# 6Amp_DCDC.net
KiCad netlist of a schematic drawn in Altium Designer
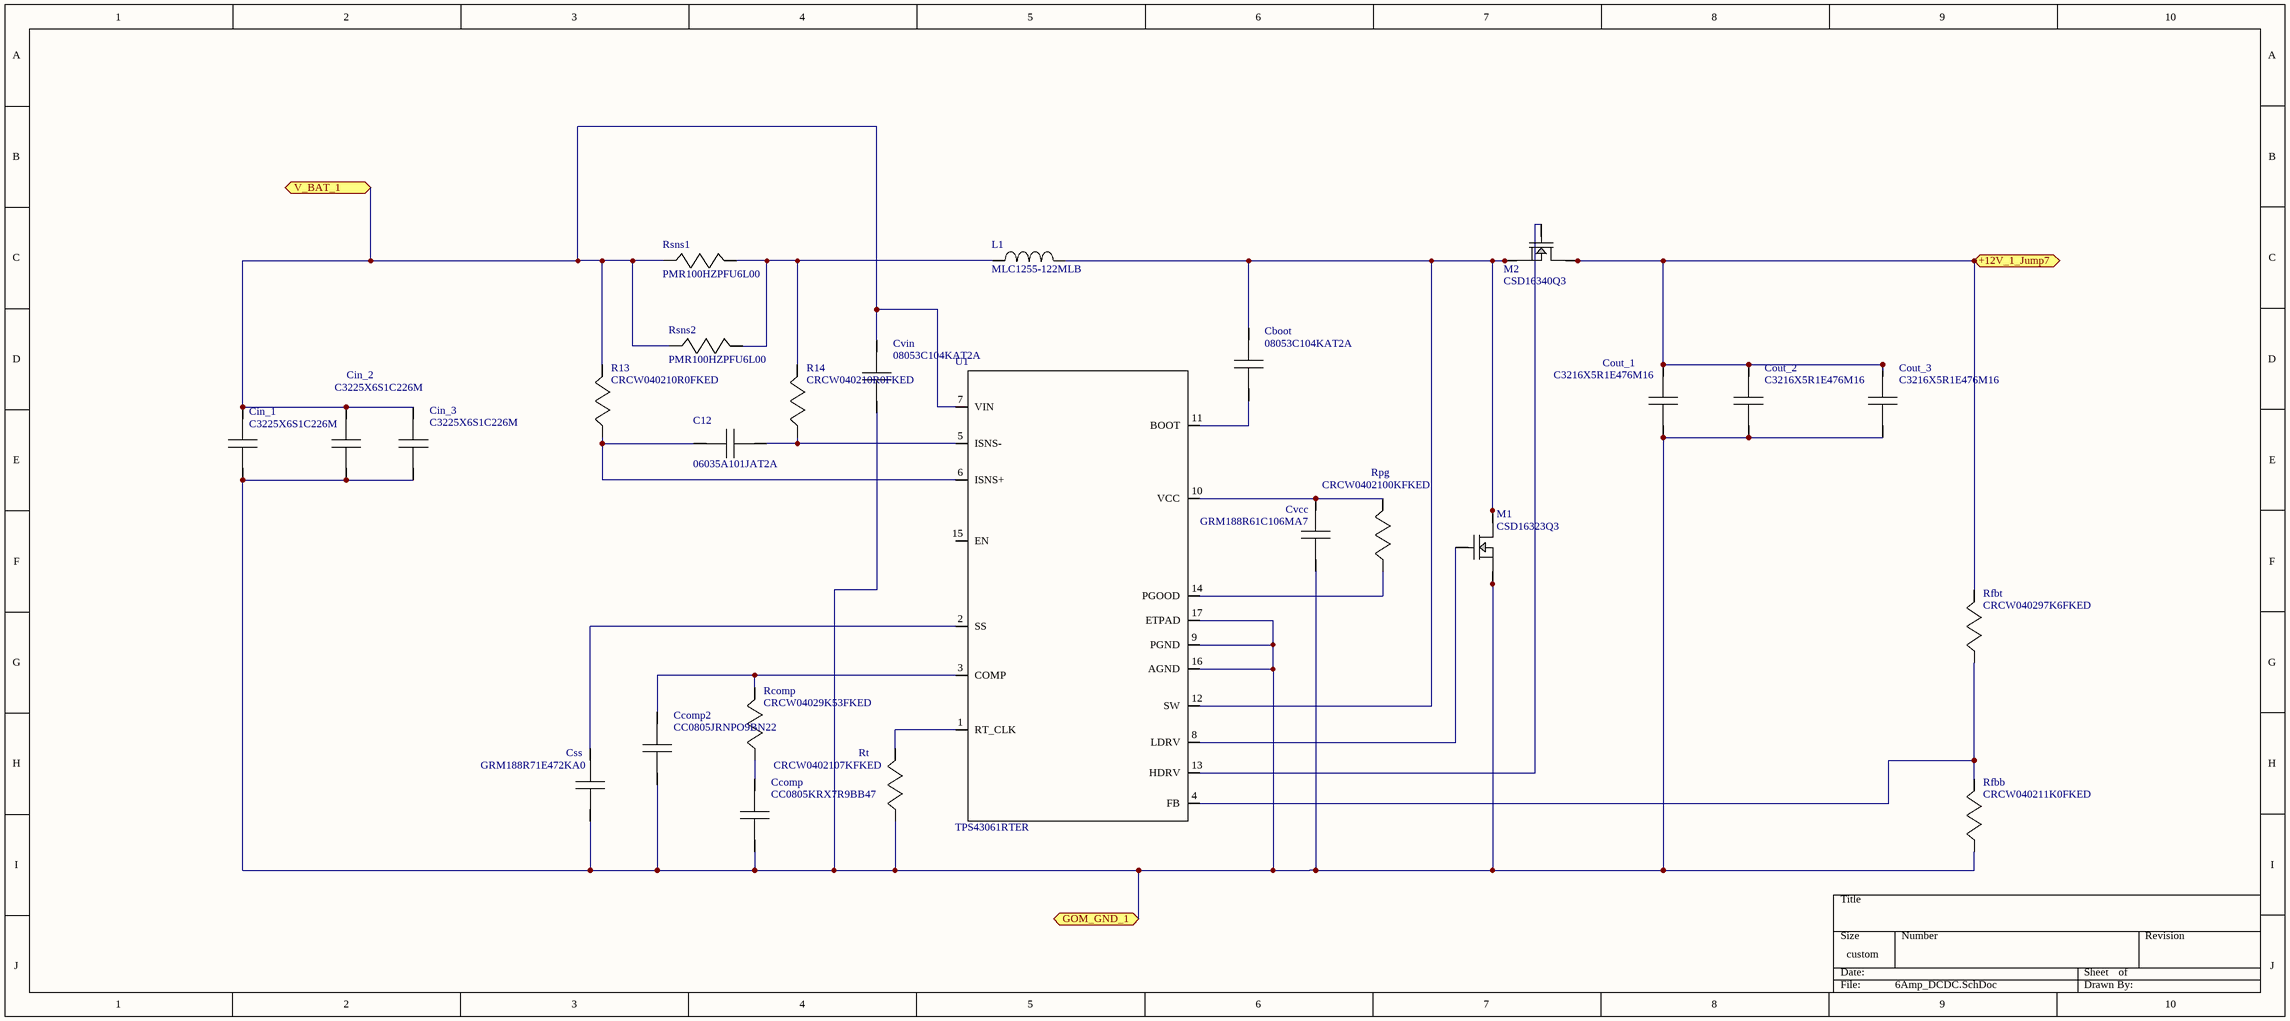
[diagram p0: 6Amp_DCDC.SchDoc]

(export (version "E")
  (design (tool "Eeschema 10.0.6"))
  (components
    (comp (ref "C12")
      (value "06035A101JAT2A")
      (footprint "0603")
      (description "Imported")
      (libsource (lib "2016-03-26_18-23-46") (part "06035A101JAT2A"))
    )
    (comp (ref "Cboot")
      (value "08053C104KAT2A")
      (footprint "0805")
      (description "Imported")
      (libsource (lib "2016-03-26_18-23-46") (part "08053C104KAT2A"))
    )
    (comp (ref "Ccomp")
      (value "CC0805KRX7R9BB47")
      (footprint "0805")
      (description "Imported")
      (fields (field (name "MANUFACTURER_PART_NUMBER") "CC0805KRX7R9BB472"))
      (libsource (lib "2016-03-26_18-23-46") (part "CC0805KRX7R9BB47"))
    )
    (comp (ref "Ccomp2")
      (value "CC0805JRNPO9BN22")
      (footprint "0805")
      (description "Imported")
      (fields (field (name "MANUFACTURER_PART_NUMBER") "CC0805JRNPO9BN221"))
      (libsource (lib "2016-03-26_18-23-46") (part "CC0805JRNPO9BN22"))
    )
    (comp (ref "Cin_1")
      (value "C3225X6S1C226M")
      (footprint "1210")
      (description "Imported")
      (libsource (lib "2016-03-26_18-23-46") (part "C3225X6S1C226M"))
    )
    (comp (ref "Cin_2")
      (value "C3225X6S1C226M")
      (footprint "1210")
      (description "Imported")
      (libsource (lib "2016-03-26_18-23-46") (part "C3225X6S1C226M"))
    )
    (comp (ref "Cin_3")
      (value "C3225X6S1C226M")
      (footprint "1210")
      (description "Imported")
      (libsource (lib "2016-03-26_18-23-46") (part "C3225X6S1C226M"))
    )
    (comp (ref "Cout_1")
      (value "C3216X5R1E476M16")
      (footprint "1206_190")
      (description "Imported")
      (fields (field (name "MANUFACTURER_PART_NUMBER") "C3216X5R1E476M160AC"))
      (libsource (lib "2016-03-26_18-23-46") (part "C3216X5R1E476M16"))
    )
    (comp (ref "Cout_2")
      (value "C3216X5R1E476M16")
      (footprint "1206_190")
      (description "Imported")
      (fields (field (name "MANUFACTURER_PART_NUMBER") "C3216X5R1E476M160AC"))
      (libsource (lib "2016-03-26_18-23-46") (part "C3216X5R1E476M16"))
    )
    (comp (ref "Cout_3")
      (value "C3216X5R1E476M16")
      (footprint "1206_190")
      (description "Imported")
      (fields (field (name "MANUFACTURER_PART_NUMBER") "C3216X5R1E476M160AC"))
      (libsource (lib "2016-03-26_18-23-46") (part "C3216X5R1E476M16"))
    )
    (comp (ref "Css")
      (value "GRM188R71E472KA0")
      (footprint "0603")
      (description "Imported")
      (fields (field (name "MANUFACTURER_PART_NUMBER") "GRM188R71E472KA01D"))
      (libsource (lib "2016-03-26_18-23-46") (part "GRM188R71E472KA0"))
    )
    (comp (ref "Cvcc")
      (value "GRM188R61C106MA7")
      (footprint "0603")
      (description "Imported")
      (fields (field (name "MANUFACTURER_PART_NUMBER") "GRM188R61C106MA73D"))
      (libsource (lib "2016-03-26_18-23-46") (part "GRM188R61C106MA7"))
    )
    (comp (ref "Cvin")
      (value "08053C104KAT2A")
      (footprint "0805")
      (description "Imported")
      (libsource (lib "2016-03-26_18-23-46") (part "08053C104KAT2A"))
    )
    (comp (ref "L1")
      (value "MLC1255-122MLB")
      (footprint "MLC1255")
      (description "Imported")
      (libsource (lib "2016-03-26_18-23-46") (part "MLC1255-122MLB"))
    )
    (comp (ref "M1")
      (value "CSD16323Q3")
      (footprint "TRANS_NexFET_Q3")
      (description "Imported")
      (libsource (lib "2016-03-26_18-23-46") (part "CSD16323Q3"))
    )
    (comp (ref "M2")
      (value "CSD16340Q3")
      (footprint "TRANS_NexFET_Q3")
      (description "Imported")
      (libsource (lib "2016-03-26_18-23-46") (part "CSD16340Q3"))
    )
    (comp (ref "R13")
      (value "CRCW040210R0FKED")
      (footprint "0402")
      (description "Imported")
      (libsource (lib "2016-03-26_18-23-46") (part "CRCW040210R0FKED"))
    )
    (comp (ref "R14")
      (value "CRCW040210R0FKED")
      (footprint "0402")
      (description "Imported")
      (libsource (lib "2016-03-26_18-23-46") (part "CRCW040210R0FKED"))
    )
    (comp (ref "Rcomp")
      (value "CRCW04029K53FKED")
      (footprint "0402")
      (description "Imported")
      (libsource (lib "2016-03-26_18-23-46") (part "CRCW04029K53FKED"))
    )
    (comp (ref "Rfbb")
      (value "CRCW040211K0FKED")
      (footprint "0402")
      (description "Imported")
      (libsource (lib "2016-03-26_18-23-46") (part "CRCW040211K0FKED"))
    )
    (comp (ref "Rfbt")
      (value "CRCW040297K6FKED")
      (footprint "0402")
      (description "Imported")
      (libsource (lib "2016-03-26_18-23-46") (part "CRCW040297K6FKED"))
    )
    (comp (ref "Rpg")
      (value "CRCW0402100KFKED")
      (footprint "0402")
      (description "Imported")
      (libsource (lib "2016-03-26_18-23-46") (part "CRCW0402100KFKED"))
    )
    (comp (ref "Rsns1")
      (value "PMR100HZPFU6L00")
      (footprint "2512")
      (description "Imported")
      (libsource (lib "2016-03-26_18-23-46") (part "PMR100HZPFU6L00"))
    )
    (comp (ref "Rsns2")
      (value "PMR100HZPFU6L00")
      (footprint "2512")
      (description "Imported")
      (libsource (lib "2016-03-26_18-23-46") (part "PMR100HZPFU6L00"))
    )
    (comp (ref "Rt")
      (value "CRCW0402107KFKED")
      (footprint "0402")
      (description "Imported")
      (libsource (lib "2016-03-26_18-23-46") (part "CRCW0402107KFKED"))
    )
    (comp (ref "U1")
      (value "TPS43061RTER")
      (footprint "S-PVQFN-N16")
      (description "Imported")
      (libsource (lib "2016-03-26_18-23-46") (part "TPS43061RTER"))
    )
  )
  (nets
    (net (code "1") (name "/+12V_1_Jump7") (class "Default")
      (node (ref "Cout_1") (pin "1") (pinfunction "1_1") (pintype "passive"))
      (node (ref "Cout_2") (pin "1") (pinfunction "1_1") (pintype "passive"))
      (node (ref "Cout_3") (pin "1") (pinfunction "1_1") (pintype "passive"))
      (node (ref "M2") (pin "5") (pinfunction "Drain_5") (pintype "passive"))
      (node (ref "M2") (pin "6") (pinfunction "Drain_6") (pintype "passive"))
      (node (ref "M2") (pin "7") (pinfunction "Drain_7") (pintype "passive"))
      (node (ref "M2") (pin "8") (pinfunction "Drain_8") (pintype "passive"))
      (node (ref "M2") (pin "9") (pinfunction "Drain_9") (pintype "passive"))
      (node (ref "Rfbt") (pin "1") (pinfunction "1_1") (pintype "passive"))
    )
    (net (code "2") (name "/GOM_GND_1") (class "Default")
      (node (ref "Ccomp") (pin "2") (pinfunction "2_2") (pintype "passive"))
      (node (ref "Ccomp2") (pin "2") (pinfunction "2_2") (pintype "passive"))
      (node (ref "Cin_1") (pin "2") (pinfunction "2_2") (pintype "passive"))
      (node (ref "Cin_2") (pin "2") (pinfunction "2_2") (pintype "passive"))
      (node (ref "Cin_3") (pin "2") (pinfunction "2_2") (pintype "passive"))
      (node (ref "Cout_1") (pin "2") (pinfunction "2_2") (pintype "passive"))
      (node (ref "Cout_2") (pin "2") (pinfunction "2_2") (pintype "passive"))
      (node (ref "Cout_3") (pin "2") (pinfunction "2_2") (pintype "passive"))
      (node (ref "Css") (pin "1") (pinfunction "1_1") (pintype "passive"))
      (node (ref "Cvcc") (pin "2") (pinfunction "2_2") (pintype "passive"))
      (node (ref "Cvin") (pin "2") (pinfunction "2_2") (pintype "passive"))
      (node (ref "M1") (pin "1") (pinfunction "Source_1") (pintype "passive"))
      (node (ref "M1") (pin "2") (pinfunction "Source_2") (pintype "passive"))
      (node (ref "M1") (pin "3") (pinfunction "Source_3") (pintype "passive"))
      (node (ref "Rfbb") (pin "2") (pinfunction "2_2") (pintype "passive"))
      (node (ref "Rt") (pin "2") (pinfunction "2_2") (pintype "passive"))
      (node (ref "U1") (pin "16") (pinfunction "AGND_16") (pintype "passive"))
      (node (ref "U1") (pin "17") (pinfunction "ETPAD_17") (pintype "passive"))
      (node (ref "U1") (pin "9") (pinfunction "PGND_9") (pintype "passive"))
    )
    (net (code "3") (name "/V_BAT_1") (class "Default")
      (node (ref "Cin_1") (pin "1") (pinfunction "1_1") (pintype "passive"))
      (node (ref "Cin_2") (pin "1") (pinfunction "1_1") (pintype "passive"))
      (node (ref "Cin_3") (pin "1") (pinfunction "1_1") (pintype "passive"))
      (node (ref "Cvin") (pin "1") (pinfunction "1_1") (pintype "passive"))
      (node (ref "R13") (pin "1") (pinfunction "1_1") (pintype "passive"))
      (node (ref "Rsns1") (pin "2") (pinfunction "2_2") (pintype "passive"))
      (node (ref "Rsns2") (pin "2") (pinfunction "2_2") (pintype "passive"))
      (node (ref "U1") (pin "7") (pinfunction "VIN_7") (pintype "passive"))
    )
    (net (code "4") (name "Net-(Ccomp-Pad1)") (class "Default")
      (node (ref "Ccomp") (pin "1") (pinfunction "1_1") (pintype "passive"))
      (node (ref "Rcomp") (pin "2") (pinfunction "2_2") (pintype "passive"))
    )
    (net (code "5") (name "Net-(L1-Pad1)") (class "Default")
      (node (ref "L1") (pin "1") (pinfunction "1_1") (pintype "passive"))
      (node (ref "R14") (pin "1") (pinfunction "1_1") (pintype "passive"))
      (node (ref "Rsns1") (pin "1") (pinfunction "1_1") (pintype "passive"))
      (node (ref "Rsns2") (pin "1") (pinfunction "1_1") (pintype "passive"))
    )
    (net (code "6") (name "Net-(M1-Gate)") (class "Default")
      (node (ref "M1") (pin "4") (pinfunction "Gate_4") (pintype "passive"))
      (node (ref "U1") (pin "8") (pinfunction "LDRV_8") (pintype "passive"))
    )
    (net (code "7") (name "Net-(M2-Gate)") (class "Default")
      (node (ref "M2") (pin "4") (pinfunction "Gate_4") (pintype "passive"))
      (node (ref "U1") (pin "13") (pinfunction "HDRV_13") (pintype "passive"))
    )
    (net (code "8") (name "Net-(U1-BOOT)") (class "Default")
      (node (ref "Cboot") (pin "2") (pinfunction "2_2") (pintype "passive"))
      (node (ref "U1") (pin "11") (pinfunction "BOOT_11") (pintype "passive"))
    )
    (net (code "9") (name "Net-(U1-COMP)") (class "Default")
      (node (ref "Ccomp2") (pin "1") (pinfunction "1_1") (pintype "passive"))
      (node (ref "Rcomp") (pin "1") (pinfunction "1_1") (pintype "passive"))
      (node (ref "U1") (pin "3") (pinfunction "COMP_3") (pintype "passive"))
    )
    (net (code "10") (name "Net-(U1-FB)") (class "Default")
      (node (ref "Rfbb") (pin "1") (pinfunction "1_1") (pintype "passive"))
      (node (ref "Rfbt") (pin "2") (pinfunction "2_2") (pintype "passive"))
      (node (ref "U1") (pin "4") (pinfunction "FB_4") (pintype "passive"))
    )
    (net (code "11") (name "Net-(U1-ISNS+)") (class "Default")
      (node (ref "C12") (pin "2") (pinfunction "2_2") (pintype "passive"))
      (node (ref "R13") (pin "2") (pinfunction "2_2") (pintype "passive"))
      (node (ref "U1") (pin "6") (pinfunction "ISNS+_6") (pintype "passive"))
    )
    (net (code "12") (name "Net-(U1-ISNS-)") (class "Default")
      (node (ref "C12") (pin "1") (pinfunction "1_1") (pintype "passive"))
      (node (ref "R14") (pin "2") (pinfunction "2_2") (pintype "passive"))
      (node (ref "U1") (pin "5") (pinfunction "ISNS-_5") (pintype "passive"))
    )
    (net (code "13") (name "Net-(U1-PGOOD)") (class "Default")
      (node (ref "Rpg") (pin "2") (pinfunction "2_2") (pintype "passive"))
      (node (ref "U1") (pin "14") (pinfunction "PGOOD_14") (pintype "passive"))
    )
    (net (code "14") (name "Net-(U1-RT_CLK)") (class "Default")
      (node (ref "Rt") (pin "1") (pinfunction "1_1") (pintype "passive"))
      (node (ref "U1") (pin "1") (pinfunction "RT_CLK_1") (pintype "passive"))
    )
    (net (code "15") (name "Net-(U1-SS)") (class "Default")
      (node (ref "Css") (pin "2") (pinfunction "2_2") (pintype "passive"))
      (node (ref "U1") (pin "2") (pinfunction "SS_2") (pintype "passive"))
    )
    (net (code "16") (name "Net-(U1-SW)") (class "Default")
      (node (ref "Cboot") (pin "1") (pinfunction "1_1") (pintype "passive"))
      (node (ref "L1") (pin "2") (pinfunction "2_2") (pintype "passive"))
      (node (ref "M1") (pin "5") (pinfunction "Drain_5") (pintype "passive"))
      (node (ref "M1") (pin "6") (pinfunction "Drain_6") (pintype "passive"))
      (node (ref "M1") (pin "7") (pinfunction "Drain_7") (pintype "passive"))
      (node (ref "M1") (pin "8") (pinfunction "Drain_8") (pintype "passive"))
      (node (ref "M1") (pin "9") (pinfunction "Drain_9") (pintype "passive"))
      (node (ref "M2") (pin "1") (pinfunction "Source_1") (pintype "passive"))
      (node (ref "M2") (pin "2") (pinfunction "Source_2") (pintype "passive"))
      (node (ref "M2") (pin "3") (pinfunction "Source_3") (pintype "passive"))
      (node (ref "U1") (pin "12") (pinfunction "SW_12") (pintype "passive"))
    )
    (net (code "17") (name "Net-(U1-VCC)") (class "Default")
      (node (ref "Cvcc") (pin "1") (pinfunction "1_1") (pintype "passive"))
      (node (ref "Rpg") (pin "1") (pinfunction "1_1") (pintype "passive"))
      (node (ref "U1") (pin "10") (pinfunction "VCC_10") (pintype "passive"))
    )
    (net (code "18") (name "unconnected-(U1-EN-Pad15)") (class "Default")
      (node (ref "U1") (pin "15") (pinfunction "EN_15") (pintype "passive"))
    )
  )
)
